# M238D.net
KiCad netlist of a schematic drawn in EAGLE
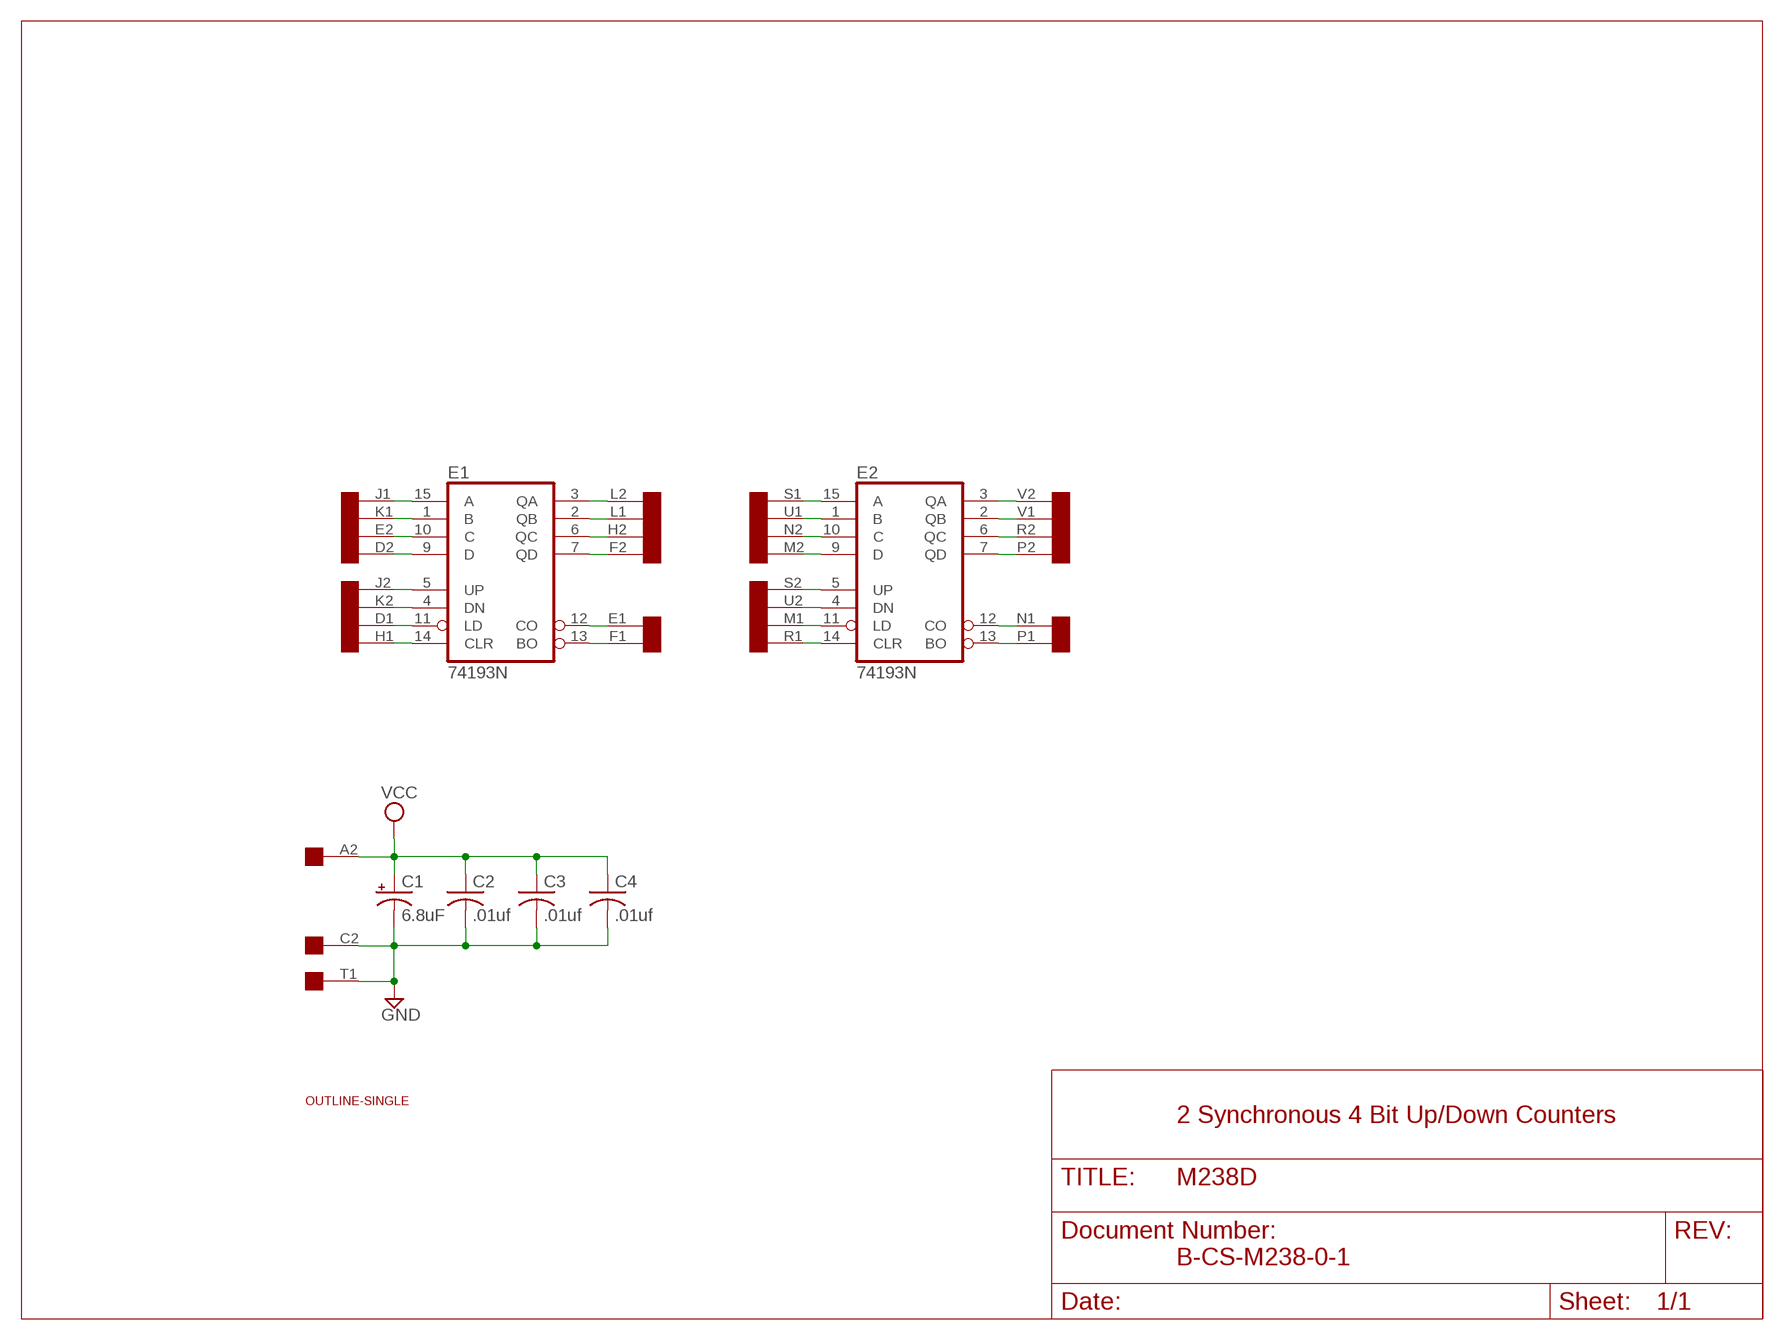
[diagram p0: schematic, sheet 1]

(export (version "E")
  (design (tool "Eeschema 10.0.6"))
  (components
    (comp (ref "C1")
      (value "6.8uF")
      (footprint "eagle-import:E12-8")
      (libsource (lib "eagle-import") (part "CPOL-USE20-8AXIAL"))
    )
    (comp (ref "C2")
      (value ".01uf")
      (footprint "eagle-import:C050-025X075")
      (libsource (lib "eagle-import") (part "C-US050-025X075"))
    )
    (comp (ref "C3")
      (value ".01uf")
      (footprint "eagle-import:C050-025X075")
      (libsource (lib "eagle-import") (part "C-US050-025X075"))
    )
    (comp (ref "C4")
      (value ".01uf")
      (footprint "eagle-import:C050-025X075")
      (libsource (lib "eagle-import") (part "C-US050-025X075"))
    )
    (comp (ref "E1")
      (value "74193N")
      (footprint "eagle-import:DIL16")
      (libsource (lib "eagle-import") (part "74192N"))
    )
    (comp (ref "E2")
      (value "74193N")
      (footprint "eagle-import:DIL16")
      (libsource (lib "eagle-import") (part "74192N"))
    )
    (comp (ref "U$1")
      (value "OUTLINE-SINGLE")
      (footprint "eagle-import:SINGLE")
      (libsource (lib "eagle-import") (part "OUTLINE-SINGLE"))
    )
    (comp (ref "U$2")
      (value "SINGLE")
      (footprint "eagle-import:EDGE-CON2")
      (libsource (lib "eagle-import") (part "SINGLE"))
    )
  )
  (nets
    (net (code "1") (name "GND") (class "Default")
      (node (ref "C1") (pin "-") (pinfunction "-_-") (pintype "passive"))
      (node (ref "C2") (pin "2") (pinfunction "2_2") (pintype "passive"))
      (node (ref "C3") (pin "2") (pinfunction "2_2") (pintype "passive"))
      (node (ref "C4") (pin "2") (pinfunction "2_2") (pintype "passive"))
      (node (ref "U$2") (pin "C2") (pinfunction "1_C2") (pintype "bidirectional"))
      (node (ref "U$2") (pin "T1") (pinfunction "1_T1") (pintype "bidirectional"))
    )
    (net (code "2") (name "Net-(E1A-A)") (class "Default")
      (node (ref "E1") (pin "15") (pinfunction "A_15") (pintype "input"))
      (node (ref "U$2") (pin "J1") (pinfunction "1_J1") (pintype "bidirectional"))
    )
    (net (code "3") (name "Net-(E1A-B)") (class "Default")
      (node (ref "E1") (pin "1") (pinfunction "B_1") (pintype "input"))
      (node (ref "U$2") (pin "K1") (pinfunction "1_K1") (pintype "bidirectional"))
    )
    (net (code "4") (name "Net-(E1A-BO)") (class "Default")
      (node (ref "E1") (pin "13") (pinfunction "BO_13") (pintype "output"))
      (node (ref "U$2") (pin "F1") (pinfunction "1_F1") (pintype "bidirectional"))
    )
    (net (code "5") (name "Net-(E1A-C)") (class "Default")
      (node (ref "E1") (pin "10") (pinfunction "C_10") (pintype "input"))
      (node (ref "U$2") (pin "E2") (pinfunction "1_E2") (pintype "bidirectional"))
    )
    (net (code "6") (name "Net-(E1A-CLR)") (class "Default")
      (node (ref "E1") (pin "14") (pinfunction "CLR_14") (pintype "input"))
      (node (ref "U$2") (pin "H1") (pinfunction "1_H1") (pintype "bidirectional"))
    )
    (net (code "7") (name "Net-(E1A-CO)") (class "Default")
      (node (ref "E1") (pin "12") (pinfunction "CO_12") (pintype "output"))
      (node (ref "U$2") (pin "E1") (pinfunction "1_E1") (pintype "bidirectional"))
    )
    (net (code "8") (name "Net-(E1A-D)") (class "Default")
      (node (ref "E1") (pin "9") (pinfunction "D_9") (pintype "input"))
      (node (ref "U$2") (pin "D2") (pinfunction "1_D2") (pintype "bidirectional"))
    )
    (net (code "9") (name "Net-(E1A-DN)") (class "Default")
      (node (ref "E1") (pin "4") (pinfunction "DN_4") (pintype "input"))
      (node (ref "U$2") (pin "K2") (pinfunction "1_K2") (pintype "bidirectional"))
    )
    (net (code "10") (name "Net-(E1A-LD)") (class "Default")
      (node (ref "E1") (pin "11") (pinfunction "LD_11") (pintype "input"))
      (node (ref "U$2") (pin "D1") (pinfunction "1_D1") (pintype "bidirectional"))
    )
    (net (code "11") (name "Net-(E1A-QA)") (class "Default")
      (node (ref "E1") (pin "3") (pinfunction "QA_3") (pintype "output"))
      (node (ref "U$2") (pin "L2") (pinfunction "1_L2") (pintype "bidirectional"))
    )
    (net (code "12") (name "Net-(E1A-QB)") (class "Default")
      (node (ref "E1") (pin "2") (pinfunction "QB_2") (pintype "output"))
      (node (ref "U$2") (pin "L1") (pinfunction "1_L1") (pintype "bidirectional"))
    )
    (net (code "13") (name "Net-(E1A-QC)") (class "Default")
      (node (ref "E1") (pin "6") (pinfunction "QC_6") (pintype "output"))
      (node (ref "U$2") (pin "H2") (pinfunction "1_H2") (pintype "bidirectional"))
    )
    (net (code "14") (name "Net-(E1A-QD)") (class "Default")
      (node (ref "E1") (pin "7") (pinfunction "QD_7") (pintype "output"))
      (node (ref "U$2") (pin "F2") (pinfunction "1_F2") (pintype "bidirectional"))
    )
    (net (code "15") (name "Net-(E1A-UP)") (class "Default")
      (node (ref "E1") (pin "5") (pinfunction "UP_5") (pintype "input"))
      (node (ref "U$2") (pin "J2") (pinfunction "1_J2") (pintype "bidirectional"))
    )
    (net (code "16") (name "Net-(E2A-A)") (class "Default")
      (node (ref "E2") (pin "15") (pinfunction "A_15") (pintype "input"))
      (node (ref "U$2") (pin "S1") (pinfunction "1_S1") (pintype "bidirectional"))
    )
    (net (code "17") (name "Net-(E2A-B)") (class "Default")
      (node (ref "E2") (pin "1") (pinfunction "B_1") (pintype "input"))
      (node (ref "U$2") (pin "U1") (pinfunction "1_U1") (pintype "bidirectional"))
    )
    (net (code "18") (name "Net-(E2A-BO)") (class "Default")
      (node (ref "E2") (pin "13") (pinfunction "BO_13") (pintype "output"))
      (node (ref "U$2") (pin "P1") (pinfunction "1_P1") (pintype "bidirectional"))
    )
    (net (code "19") (name "Net-(E2A-C)") (class "Default")
      (node (ref "E2") (pin "10") (pinfunction "C_10") (pintype "input"))
      (node (ref "U$2") (pin "N2") (pinfunction "1_N2") (pintype "bidirectional"))
    )
    (net (code "20") (name "Net-(E2A-CLR)") (class "Default")
      (node (ref "E2") (pin "14") (pinfunction "CLR_14") (pintype "input"))
      (node (ref "U$2") (pin "R1") (pinfunction "1_R1") (pintype "bidirectional"))
    )
    (net (code "21") (name "Net-(E2A-CO)") (class "Default")
      (node (ref "E2") (pin "12") (pinfunction "CO_12") (pintype "output"))
      (node (ref "U$2") (pin "N1") (pinfunction "1_N1") (pintype "bidirectional"))
    )
    (net (code "22") (name "Net-(E2A-D)") (class "Default")
      (node (ref "E2") (pin "9") (pinfunction "D_9") (pintype "input"))
      (node (ref "U$2") (pin "M2") (pinfunction "1_M2") (pintype "bidirectional"))
    )
    (net (code "23") (name "Net-(E2A-DN)") (class "Default")
      (node (ref "E2") (pin "4") (pinfunction "DN_4") (pintype "input"))
      (node (ref "U$2") (pin "U2") (pinfunction "1_U2") (pintype "bidirectional"))
    )
    (net (code "24") (name "Net-(E2A-LD)") (class "Default")
      (node (ref "E2") (pin "11") (pinfunction "LD_11") (pintype "input"))
      (node (ref "U$2") (pin "M1") (pinfunction "1_M1") (pintype "bidirectional"))
    )
    (net (code "25") (name "Net-(E2A-QA)") (class "Default")
      (node (ref "E2") (pin "3") (pinfunction "QA_3") (pintype "output"))
      (node (ref "U$2") (pin "V2") (pinfunction "1_V2") (pintype "bidirectional"))
    )
    (net (code "26") (name "Net-(E2A-QB)") (class "Default")
      (node (ref "E2") (pin "2") (pinfunction "QB_2") (pintype "output"))
      (node (ref "U$2") (pin "V1") (pinfunction "1_V1") (pintype "bidirectional"))
    )
    (net (code "27") (name "Net-(E2A-QC)") (class "Default")
      (node (ref "E2") (pin "6") (pinfunction "QC_6") (pintype "output"))
      (node (ref "U$2") (pin "R2") (pinfunction "1_R2") (pintype "bidirectional"))
    )
    (net (code "28") (name "Net-(E2A-QD)") (class "Default")
      (node (ref "E2") (pin "7") (pinfunction "QD_7") (pintype "output"))
      (node (ref "U$2") (pin "P2") (pinfunction "1_P2") (pintype "bidirectional"))
    )
    (net (code "29") (name "Net-(E2A-UP)") (class "Default")
      (node (ref "E2") (pin "5") (pinfunction "UP_5") (pintype "input"))
      (node (ref "U$2") (pin "S2") (pinfunction "1_S2") (pintype "bidirectional"))
    )
    (net (code "30") (name "VCC") (class "Default")
      (node (ref "C1") (pin "+") (pinfunction "+_+") (pintype "passive"))
      (node (ref "C2") (pin "1") (pinfunction "1_1") (pintype "passive"))
      (node (ref "C3") (pin "1") (pinfunction "1_1") (pintype "passive"))
      (node (ref "C4") (pin "1") (pinfunction "1_1") (pintype "passive"))
      (node (ref "U$2") (pin "A2") (pinfunction "1_A2") (pintype "bidirectional"))
    )
  )
)
